# USB_OTG_FS.net
KiCad netlist of a schematic drawn in Altium Designer
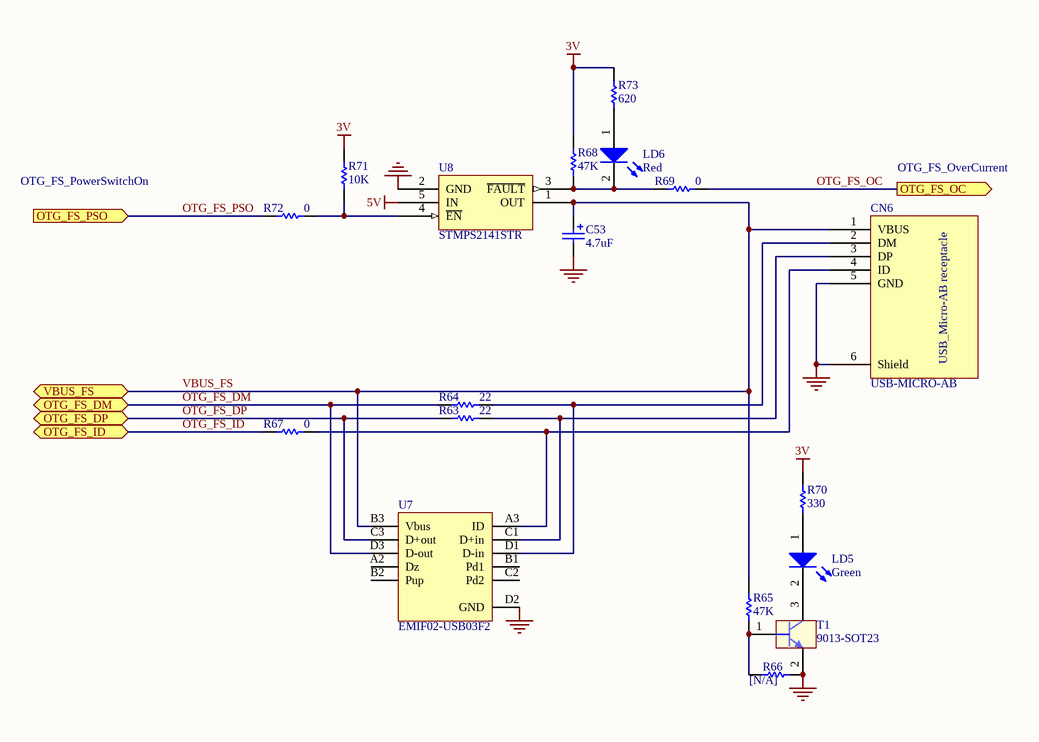
[diagram p0: USB_OTG_FS.SchDoc]

(export (version "E")
  (design (tool "Eeschema 10.0.6"))
  (components
    (comp (ref "C53")
      (value "4.7uF")
      (footprint "TAN-A")
      (description "Polarized Capacitor (Radial)")
      (fields (field (name "PUBLISHER") "Altium Limited"))
      (libsource (lib "Miscellaneous Devices") (part "Cap Pol1"))
    )
    (comp (ref "CN6")
      (value "USB-MICRO-AB")
      (footprint "CON_USBMICROAB_MOLEX_47590-0001_H3")
      (description "USB-MICRO-AB, 47590-0001, SMT, MOLEX")
      (libsource (lib "MCD_TOOLS") (part "USB-MICRO-AB"))
    )
    (comp (ref "LD5")
      (value "Green")
      (footprint "0603D")
      (description "Typical RED, GREEN, YELLOW, AMBER GaAs LED")
      (fields (field (name "PUBLISHER") "Altium Limited"))
      (libsource (lib "Miscellaneous Devices") (part "LED2"))
    )
    (comp (ref "LD6")
      (value "Red")
      (footprint "0603D")
      (description "Typical RED, GREEN, YELLOW, AMBER GaAs LED")
      (fields (field (name "PUBLISHER") "Altium Limited"))
      (libsource (lib "Miscellaneous Devices") (part "LED2"))
    )
    (comp (ref "R63")
      (value "22")
      (footprint "0402R")
      (description "Resistor 0402 / 0603 / 0805")
      (libsource (lib "MCD_TOOLS") (part "Resistor_ST"))
    )
    (comp (ref "R64")
      (value "22")
      (footprint "0402R")
      (description "Resistor 0402 / 0603 / 0805")
      (libsource (lib "MCD_TOOLS") (part "Resistor_ST"))
    )
    (comp (ref "R65")
      (value "47K")
      (footprint "0402R")
      (description "Resistor 0402 / 0603 / 0805")
      (libsource (lib "MCD_TOOLS") (part "Resistor_ST"))
    )
    (comp (ref "R66")
      (value "[N/A]")
      (footprint "0402R")
      (description "Resistor 0402 / 0603 / 0805")
      (libsource (lib "MCD_TOOLS") (part "Resistor_ST"))
    )
    (comp (ref "R67")
      (value "0")
      (footprint "0402R")
      (description "Resistor 0402 / 0603 / 0805")
      (libsource (lib "MCD_TOOLS") (part "Resistor_ST"))
    )
    (comp (ref "R68")
      (value "47K")
      (footprint "0402R")
      (description "Resistor 0402 / 0603 / 0805")
      (libsource (lib "MCD_TOOLS") (part "Resistor_ST"))
    )
    (comp (ref "R69")
      (value "0")
      (footprint "0402R")
      (description "Resistor 0402 / 0603 / 0805")
      (libsource (lib "MCD_TOOLS") (part "Resistor_ST"))
    )
    (comp (ref "R70")
      (value "330")
      (footprint "0603R")
      (description "Resistor 0402 / 0603 / 0805")
      (libsource (lib "MCD_TOOLS") (part "Resistor_ST"))
    )
    (comp (ref "R71")
      (value "10K")
      (footprint "0402R")
      (description "Resistor 0402 / 0603 / 0805")
      (libsource (lib "MCD_TOOLS") (part "Resistor_ST"))
    )
    (comp (ref "R72")
      (value "0")
      (footprint "0402R")
      (description "Resistor 0402 / 0603 / 0805")
      (libsource (lib "MCD_TOOLS") (part "Resistor_ST"))
    )
    (comp (ref "R73")
      (value "620")
      (footprint "0603R")
      (description "Resistor 0402 / 0603 / 0805")
      (libsource (lib "MCD_TOOLS") (part "Resistor_ST"))
    )
    (comp (ref "T1")
      (value "9013-SOT23")
      (footprint "SOT-23")
      (description "NPN Bipolar Transistor")
      (libsource (lib "MCD_TOOLS") (part "9013-SOT23"))
    )
    (comp (ref "U7")
      (value "EMIF02-USB03F2")
      (footprint "Flip Chip")
      (description "2-line IPAD, EMI filter including ESD protection")
      (libsource (lib "MCD_TOOLS") (part "EMIF02-USB03F2"))
    )
    (comp (ref "U8")
      (value "STMPS2141STR")
      (footprint "SOT23-5L")
      (description "Enhanced single channel power switches")
      (libsource (lib "MCD_TOOLS") (part "STMPS2141STR"))
    )
  )
  (nets
    (net (code "1") (name "/OTG_FS_DM") (class "Default")
      (node (ref "R64") (pin "1") (pinfunction "1_1") (pintype "passive"))
      (node (ref "U7") (pin "D3") (pinfunction "D-out_D3") (pintype "passive"))
    )
    (net (code "2") (name "/OTG_FS_DP") (class "Default")
      (node (ref "R63") (pin "1") (pinfunction "1_1") (pintype "passive"))
      (node (ref "U7") (pin "C3") (pinfunction "D+out_C3") (pintype "passive"))
    )
    (net (code "3") (name "/OTG_FS_ID") (class "Default")
      (node (ref "R67") (pin "1") (pinfunction "1_1") (pintype "passive"))
    )
    (net (code "4") (name "/OTG_FS_OC") (class "Default")
      (node (ref "R69") (pin "2") (pinfunction "2_2") (pintype "passive"))
    )
    (net (code "5") (name "/OTG_FS_PSO") (class "Default")
      (node (ref "R72") (pin "1") (pinfunction "1_1") (pintype "passive"))
    )
    (net (code "6") (name "/VBUS_FS") (class "Default")
      (node (ref "C53") (pin "1") (pinfunction "1_1") (pintype "passive"))
      (node (ref "CN6") (pin "1") (pinfunction "VBUS_1") (pintype "passive"))
      (node (ref "R65") (pin "2") (pinfunction "2_2") (pintype "passive"))
      (node (ref "U7") (pin "B3") (pinfunction "Vbus_B3") (pintype "passive"))
      (node (ref "U8") (pin "1") (pinfunction "OUT_1") (pintype "passive"))
    )
    (net (code "7") (name "3V") (class "Default")
      (node (ref "R68") (pin "2") (pinfunction "2_2") (pintype "passive"))
      (node (ref "R70") (pin "2") (pinfunction "2_2") (pintype "passive"))
      (node (ref "R71") (pin "2") (pinfunction "2_2") (pintype "passive"))
      (node (ref "R73") (pin "2") (pinfunction "2_2") (pintype "passive"))
    )
    (net (code "8") (name "5V") (class "Default")
      (node (ref "U8") (pin "5") (pinfunction "IN_5") (pintype "passive"))
    )
    (net (code "9") (name "GND") (class "Default")
      (node (ref "C53") (pin "2") (pinfunction "2_2") (pintype "passive"))
      (node (ref "CN6") (pin "5") (pinfunction "GND_5") (pintype "passive"))
      (node (ref "CN6") (pin "6") (pinfunction "Shield_6") (pintype "passive"))
      (node (ref "R66") (pin "2") (pinfunction "2_2") (pintype "passive"))
      (node (ref "T1") (pin "2") (pinfunction "E_2") (pintype "passive"))
      (node (ref "U7") (pin "D2") (pinfunction "GND_D2") (pintype "passive"))
      (node (ref "U8") (pin "2") (pinfunction "GND_2") (pintype "passive"))
    )
    (net (code "10") (name "Net-(CN6-DM)") (class "Default")
      (node (ref "CN6") (pin "2") (pinfunction "DM_2") (pintype "passive"))
      (node (ref "R64") (pin "2") (pinfunction "2_2") (pintype "passive"))
      (node (ref "U7") (pin "D1") (pinfunction "D-in_D1") (pintype "passive"))
    )
    (net (code "11") (name "Net-(CN6-DP)") (class "Default")
      (node (ref "CN6") (pin "3") (pinfunction "DP_3") (pintype "passive"))
      (node (ref "R63") (pin "2") (pinfunction "2_2") (pintype "passive"))
      (node (ref "U7") (pin "C1") (pinfunction "D+in_C1") (pintype "passive"))
    )
    (net (code "12") (name "Net-(CN6-ID)") (class "Default")
      (node (ref "CN6") (pin "4") (pinfunction "ID_4") (pintype "passive"))
      (node (ref "R67") (pin "2") (pinfunction "2_2") (pintype "passive"))
      (node (ref "U7") (pin "A3") (pinfunction "ID_A3") (pintype "passive"))
    )
    (net (code "13") (name "Net-(LD5-A)") (class "Default")
      (node (ref "LD5") (pin "1") (pinfunction "A_1") (pintype "passive"))
      (node (ref "R70") (pin "1") (pinfunction "1_1") (pintype "passive"))
    )
    (net (code "14") (name "Net-(LD5-K)") (class "Default")
      (node (ref "LD5") (pin "2") (pinfunction "K_2") (pintype "passive"))
      (node (ref "T1") (pin "3") (pinfunction "C_3") (pintype "passive"))
    )
    (net (code "15") (name "Net-(LD6-A)") (class "Default")
      (node (ref "LD6") (pin "1") (pinfunction "A_1") (pintype "passive"))
      (node (ref "R73") (pin "1") (pinfunction "1_1") (pintype "passive"))
    )
    (net (code "16") (name "Net-(LD6-K)") (class "Default")
      (node (ref "LD6") (pin "2") (pinfunction "K_2") (pintype "passive"))
      (node (ref "R68") (pin "1") (pinfunction "1_1") (pintype "passive"))
      (node (ref "R69") (pin "1") (pinfunction "1_1") (pintype "passive"))
      (node (ref "U8") (pin "3") (pinfunction "~{FAULT}_3") (pintype "output"))
    )
    (net (code "17") (name "Net-(T1-B)") (class "Default")
      (node (ref "R65") (pin "1") (pinfunction "1_1") (pintype "passive"))
      (node (ref "R66") (pin "1") (pinfunction "1_1") (pintype "passive"))
      (node (ref "T1") (pin "1") (pinfunction "B_1") (pintype "passive"))
    )
    (net (code "18") (name "Net-(U8-~{EN})") (class "Default")
      (node (ref "R71") (pin "1") (pinfunction "1_1") (pintype "passive"))
      (node (ref "R72") (pin "2") (pinfunction "2_2") (pintype "passive"))
      (node (ref "U8") (pin "4") (pinfunction "~{EN}_4") (pintype "input"))
    )
    (net (code "19") (name "unconnected-(U7-Dz-PadA2)") (class "Default")
      (node (ref "U7") (pin "A2") (pinfunction "Dz_A2") (pintype "passive"))
    )
    (net (code "20") (name "unconnected-(U7-Pd1-PadB1)") (class "Default")
      (node (ref "U7") (pin "B1") (pinfunction "Pd1_B1") (pintype "passive"))
    )
    (net (code "21") (name "unconnected-(U7-Pd2-PadC2)") (class "Default")
      (node (ref "U7") (pin "C2") (pinfunction "Pd2_C2") (pintype "passive"))
    )
    (net (code "22") (name "unconnected-(U7-Pup-PadB2)") (class "Default")
      (node (ref "U7") (pin "B2") (pinfunction "Pup_B2") (pintype "passive"))
    )
  )
)
